# feather_v4.net
KiCad netlist of a schematic drawn in EAGLE
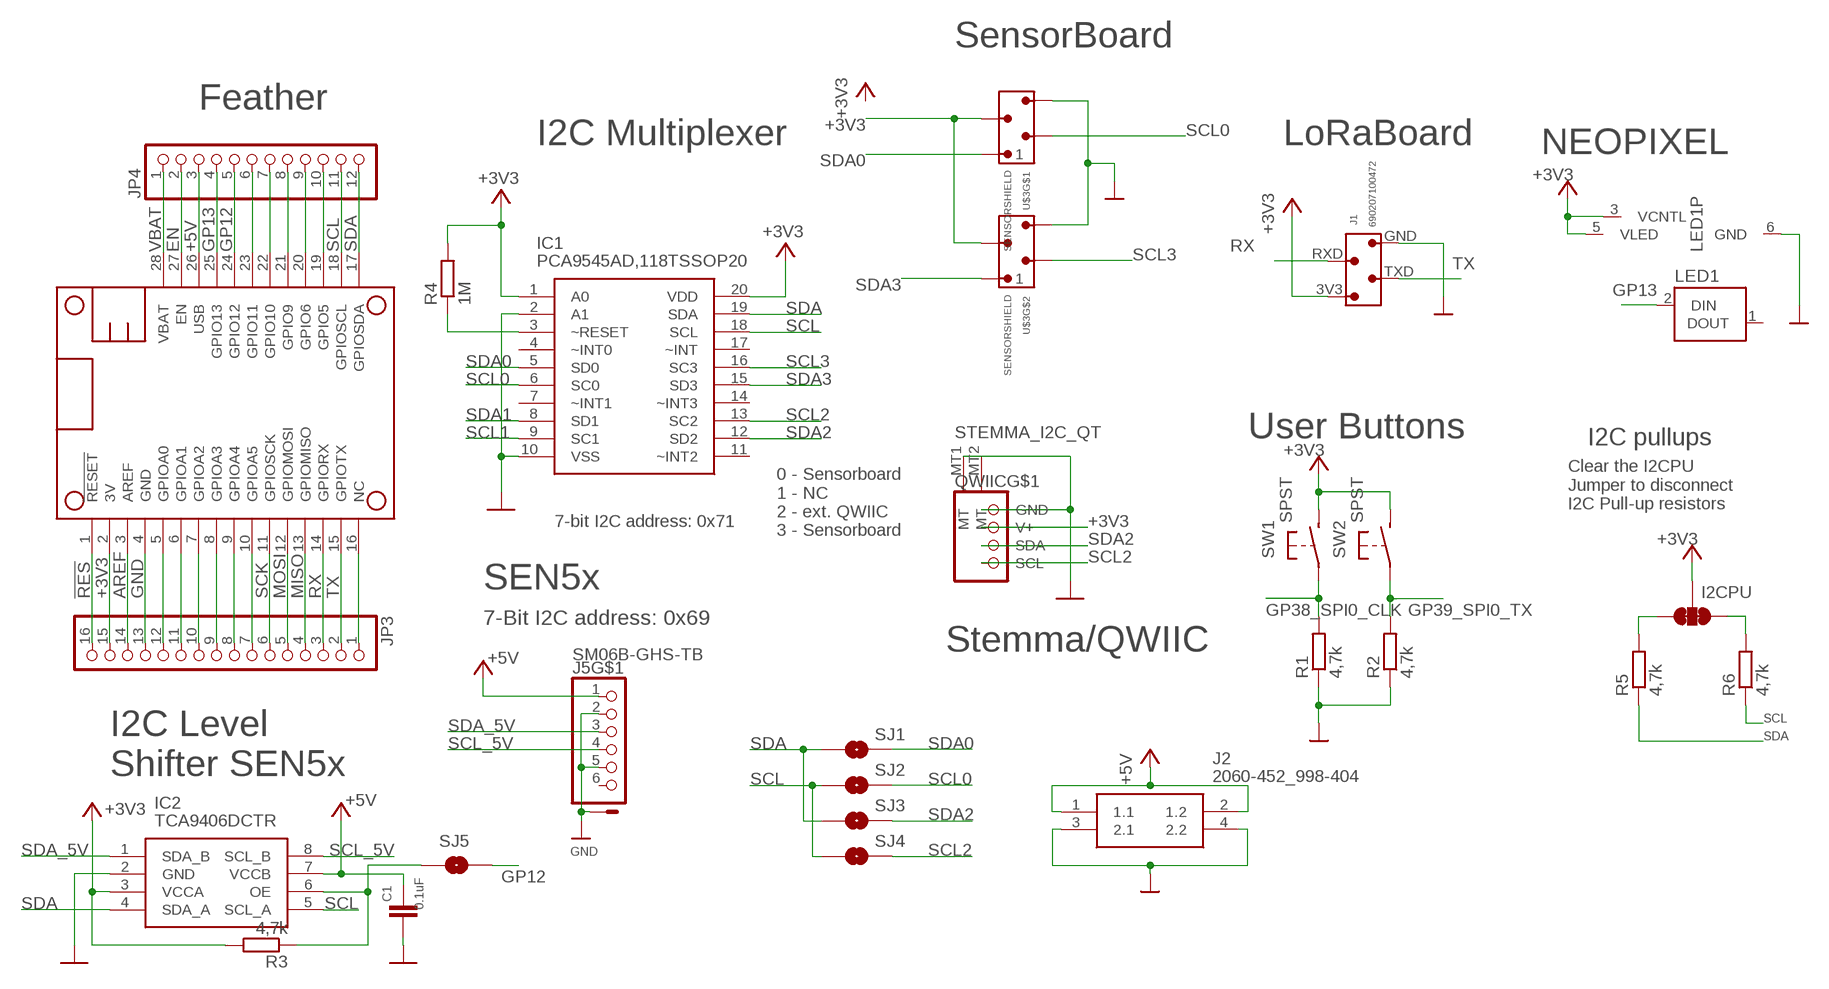
[diagram p0: schematic, sheet 1]

(export (version "E")
  (design (tool "Eeschema 10.0.6"))
  (components
    (comp (ref "C1")
      (value "0.1uF")
      (footprint "eagle-import:C0603")
      (libsource (lib "eagle-import") (part "C-EUC0603"))
    )
    (comp (ref "I2CPU")
      (value "I2C PU")
      (footprint "eagle-import:SMT-JUMPER_3_2-NC_TRACE_SILK")
      (libsource (lib "eagle-import") (part "JUMPER-SMT_3_2-NC_TRACE_SILK"))
    )
    (comp (ref "IC1")
      (value "PCA9545AD,118TSSOP20")
      (footprint "eagle-import:TSSOP20")
      (libsource (lib "eagle-import") (part "PCA9545AD,118TSSOP20"))
    )
    (comp (ref "IC2")
      (value "TCA9406DCTR")
      (footprint "eagle-import:SOP65P400X130-8N")
      (fields (field (name "MOUSER_PART_NUMBER") "595-TCA9406DCTR"))
      (libsource (lib "eagle-import") (part "TCA9406DCTR"))
    )
    (comp (ref "J1")
      (value "690207100472")
      (footprint "eagle-import:LORASHIELD")
      (libsource (lib "eagle-import") (part "LORASHIELD"))
    )
    (comp (ref "J2")
      (value "2060-452_998-404")
      (footprint "eagle-import:2060452998404")
      (fields (field (name "ARROW_PART_NUMBER") "2060-452/998-404"))
      (libsource (lib "eagle-import") (part "2060-452_998-404"))
    )
    (comp (ref "J5")
      (value "SM06B-GHS-TB")
      (footprint "eagle-import:JST-PH-06-SMD")
      (libsource (lib "eagle-import") (part "JST-PH-06-SMDSMD"))
    )
    (comp (ref "JP3")
      (value "HEADER-1X16_76MIL")
      (footprint "eagle-import:1X16_ROUND_76MIL")
      (libsource (lib "eagle-import") (part "HEADER-1X16_76MIL"))
    )
    (comp (ref "JP4")
      (value "HEADER-1X1276MIL")
      (footprint "eagle-import:1X12_ROUND_76MIL")
      (libsource (lib "eagle-import") (part "HEADER-1X1276MIL"))
    )
    (comp (ref "LED1")
      (value "WS2812WS2812")
      (footprint "eagle-import:WS2812")
      (libsource (lib "eagle-import") (part "WS2812WS2812"))
    )
    (comp (ref "MS1")
      (value "FEATHERWING_NODIM")
      (footprint "eagle-import:FEATHERWING_DIM")
      (libsource (lib "eagle-import") (part "FEATHERWING_NODIM"))
    )
    (comp (ref "QWIIC")
      (value "STEMMA_I2C_QT")
      (footprint "eagle-import:JST_SH4")
      (libsource (lib "eagle-import") (part "STEMMA_I2C_QT"))
    )
    (comp (ref "R1")
      (value "4,7k")
      (footprint "eagle-import:R0603")
      (libsource (lib "eagle-import") (part "R-EU_R0603"))
    )
    (comp (ref "R2")
      (value "4,7k")
      (footprint "eagle-import:R0603")
      (libsource (lib "eagle-import") (part "R-EU_R0603"))
    )
    (comp (ref "R3")
      (value "4,7k")
      (footprint "eagle-import:R0603")
      (libsource (lib "eagle-import") (part "R-EU_R0603"))
    )
    (comp (ref "R4")
      (value "1M")
      (footprint "eagle-import:R0603")
      (libsource (lib "eagle-import") (part "R-EU_R0603"))
    )
    (comp (ref "R5")
      (value "4,7k")
      (footprint "eagle-import:R0603")
      (libsource (lib "eagle-import") (part "R-EU_R0603"))
    )
    (comp (ref "R6")
      (value "4,7k")
      (footprint "eagle-import:R0603")
      (libsource (lib "eagle-import") (part "R-EU_R0603"))
    )
    (comp (ref "SJ1")
      (value "SOLDERJUMPERNO")
      (footprint "eagle-import:SJ_2S-NO")
      (libsource (lib "eagle-import") (part "SOLDERJUMPERNO"))
    )
    (comp (ref "SJ2")
      (value "SOLDERJUMPERNO")
      (footprint "eagle-import:SJ_2S-NO")
      (libsource (lib "eagle-import") (part "SOLDERJUMPERNO"))
    )
    (comp (ref "SJ3")
      (value "SOLDERJUMPERNO")
      (footprint "eagle-import:SJ_2S-NO")
      (libsource (lib "eagle-import") (part "SOLDERJUMPERNO"))
    )
    (comp (ref "SJ4")
      (value "SOLDERJUMPERNO")
      (footprint "eagle-import:SJ_2S-NO")
      (libsource (lib "eagle-import") (part "SOLDERJUMPERNO"))
    )
    (comp (ref "SJ5")
      (value "SOLDERJUMPERNO")
      (footprint "eagle-import:SJ_2S-NO")
      (libsource (lib "eagle-import") (part "SOLDERJUMPERNO"))
    )
    (comp (ref "SW1")
      (value "SPST")
      (footprint "eagle-import:DTSM-32S-B")
      (libsource (lib "eagle-import") (part "SPST"))
    )
    (comp (ref "SW2")
      (value "SPST")
      (footprint "eagle-import:DTSM-32S-B")
      (libsource (lib "eagle-import") (part "SPST"))
    )
    (comp (ref "U$3")
      (value "SENSORSHIELD")
      (footprint "eagle-import:SENSORSHIELD")
      (libsource (lib "eagle-import") (part "SENSORSHIELD"))
    )
  )
  (nets
    (net (code "1") (name "+3V3") (class "Default")
      (node (ref "I2CPU") (pin "2") (pinfunction "2_2") (pintype "passive"))
      (node (ref "IC1") (pin "1") (pinfunction "A0_1") (pintype "bidirectional"))
      (node (ref "IC1") (pin "20") (pinfunction "VDD_20") (pintype "bidirectional"))
      (node (ref "IC2") (pin "3") (pinfunction "VCCA_3") (pintype "bidirectional"))
      (node (ref "J1") (pin "3V3") (pinfunction "4_3V3") (pintype "passive"))
      (node (ref "JP3") (pin "15") (pinfunction "15_15") (pintype "passive"))
      (node (ref "LED1") (pin "3") (pinfunction "VCNTL_3") (pintype "power_in"))
      (node (ref "LED1") (pin "5") (pinfunction "VLED_5") (pintype "power_in"))
      (node (ref "MS1") (pin "2") (pinfunction "3V_2") (pintype "power_in"))
      (node (ref "QWIIC") (pin "2") (pinfunction "V+_2") (pintype "passive"))
      (node (ref "R3") (pin "2") (pinfunction "2_2") (pintype "passive"))
      (node (ref "R4") (pin "2") (pinfunction "2_2") (pintype "passive"))
      (node (ref "SW1") (pin "P$2") (pinfunction "S_P$2") (pintype "passive"))
      (node (ref "SW2") (pin "P$2") (pinfunction "S_P$2") (pintype "passive"))
      (node (ref "U$3") (pin "3V3_1") (pinfunction "3_3V3_1") (pintype "passive"))
      (node (ref "U$3") (pin "3V3_2") (pinfunction "3_3V3_2") (pintype "passive"))
    )
    (net (code "2") (name "+5V") (class "Default")
      (node (ref "C1") (pin "1") (pinfunction "1_1") (pintype "passive"))
      (node (ref "IC2") (pin "7") (pinfunction "VCCB_7") (pintype "bidirectional"))
      (node (ref "J2") (pin "1") (pinfunction "1.1_1") (pintype "bidirectional"))
      (node (ref "J2") (pin "2") (pinfunction "1.2_2") (pintype "bidirectional"))
      (node (ref "J5") (pin "1") (pinfunction "1_1") (pintype "passive"))
      (node (ref "JP4") (pin "3") (pinfunction "3_3") (pintype "passive"))
      (node (ref "MS1") (pin "26") (pinfunction "USB_26") (pintype "power_in"))
    )
    (net (code "3") (name "/AREF") (class "Default")
      (node (ref "JP3") (pin "14") (pinfunction "14_14") (pintype "passive"))
      (node (ref "MS1") (pin "3") (pinfunction "AREF_3") (pintype "passive"))
    )
    (net (code "4") (name "/EN") (class "Default")
      (node (ref "JP4") (pin "2") (pinfunction "2_2") (pintype "passive"))
      (node (ref "MS1") (pin "27") (pinfunction "EN_27") (pintype "passive"))
    )
    (net (code "5") (name "/GP12") (class "Default")
      (node (ref "JP4") (pin "5") (pinfunction "5_5") (pintype "passive"))
      (node (ref "MS1") (pin "24") (pinfunction "GPIO12_24") (pintype "bidirectional"))
      (node (ref "SJ5") (pin "2") (pinfunction "2_2") (pintype "passive"))
    )
    (net (code "6") (name "/GP13") (class "Default")
      (node (ref "JP4") (pin "4") (pinfunction "4_4") (pintype "passive"))
      (node (ref "LED1") (pin "2") (pinfunction "DIN_2") (pintype "input"))
      (node (ref "MS1") (pin "25") (pinfunction "GPIO13_25") (pintype "bidirectional"))
    )
    (net (code "7") (name "/GP38_SPI0_CLK") (class "Default")
      (node (ref "R1") (pin "2") (pinfunction "2_2") (pintype "passive"))
      (node (ref "SW1") (pin "P$1") (pinfunction "P_P$1") (pintype "passive"))
    )
    (net (code "8") (name "/GP39_SPI0_TX") (class "Default")
      (node (ref "R2") (pin "2") (pinfunction "2_2") (pintype "passive"))
      (node (ref "SW2") (pin "P$1") (pinfunction "P_P$1") (pintype "passive"))
    )
    (net (code "9") (name "/MISO") (class "Default")
      (node (ref "JP3") (pin "4") (pinfunction "4_4") (pintype "passive"))
      (node (ref "MS1") (pin "13") (pinfunction "GPIOMISO_13") (pintype "bidirectional"))
    )
    (net (code "10") (name "/MOSI") (class "Default")
      (node (ref "JP3") (pin "5") (pinfunction "5_5") (pintype "passive"))
      (node (ref "MS1") (pin "12") (pinfunction "GPIOMOSI_12") (pintype "bidirectional"))
    )
    (net (code "11") (name "/SCK") (class "Default")
      (node (ref "JP3") (pin "6") (pinfunction "6_6") (pintype "passive"))
      (node (ref "MS1") (pin "11") (pinfunction "GPIOSCK_11") (pintype "bidirectional"))
    )
    (net (code "12") (name "/SCL1") (class "Default")
      (node (ref "IC1") (pin "9") (pinfunction "SC1_9") (pintype "bidirectional"))
    )
    (net (code "13") (name "/SCL_5V") (class "Default")
      (node (ref "IC2") (pin "8") (pinfunction "SCL_B_8") (pintype "bidirectional"))
      (node (ref "J5") (pin "4") (pinfunction "4_4") (pintype "passive"))
    )
    (net (code "14") (name "/SDA1") (class "Default")
      (node (ref "IC1") (pin "8") (pinfunction "SD1_8") (pintype "bidirectional"))
    )
    (net (code "15") (name "/SDA_5V") (class "Default")
      (node (ref "IC2") (pin "1") (pinfunction "SDA_B_1") (pintype "bidirectional"))
      (node (ref "J5") (pin "3") (pinfunction "3_3") (pintype "passive"))
    )
    (net (code "16") (name "/VBAT") (class "Default")
      (node (ref "JP4") (pin "1") (pinfunction "1_1") (pintype "passive"))
      (node (ref "MS1") (pin "28") (pinfunction "VBAT_28") (pintype "power_in"))
    )
    (net (code "17") (name "/~{RES}") (class "Default")
      (node (ref "JP3") (pin "16") (pinfunction "16_16") (pintype "passive"))
      (node (ref "MS1") (pin "1") (pinfunction "~{RESET}_1") (pintype "input"))
    )
    (net (code "18") (name "GND") (class "Default")
      (node (ref "C1") (pin "2") (pinfunction "2_2") (pintype "passive"))
      (node (ref "IC1") (pin "10") (pinfunction "VSS_10") (pintype "bidirectional"))
      (node (ref "IC1") (pin "2") (pinfunction "A1_2") (pintype "bidirectional"))
      (node (ref "IC2") (pin "2") (pinfunction "GND_2") (pintype "bidirectional"))
      (node (ref "J1") (pin "GND") (pinfunction "1_GND") (pintype "passive"))
      (node (ref "J2") (pin "3") (pinfunction "2.1_3") (pintype "bidirectional"))
      (node (ref "J2") (pin "4") (pinfunction "2.2_4") (pintype "bidirectional"))
      (node (ref "J5") (pin "2") (pinfunction "2_2") (pintype "passive"))
      (node (ref "J5") (pin "5") (pinfunction "5_5") (pintype "passive"))
      (node (ref "J5") (pin "7") (pinfunction "S_7") (pintype "passive"))
      (node (ref "J5") (pin "8") (pinfunction "S_8") (pintype "passive"))
      (node (ref "JP3") (pin "12") (pinfunction "12_12") (pintype "passive"))
      (node (ref "JP3") (pin "13") (pinfunction "13_13") (pintype "passive"))
      (node (ref "LED1") (pin "6") (pinfunction "GND_6") (pintype "power_in"))
      (node (ref "MS1") (pin "4") (pinfunction "GND_4") (pintype "power_in"))
      (node (ref "MS1") (pin "5") (pinfunction "GPIOA0_5") (pintype "bidirectional"))
      (node (ref "QWIIC") (pin "1") (pinfunction "GND_1") (pintype "passive"))
      (node (ref "QWIIC") (pin "MT1") (pinfunction "MT_MT1") (pintype "bidirectional"))
      (node (ref "QWIIC") (pin "MT2") (pinfunction "MT_MT2") (pintype "bidirectional"))
      (node (ref "R1") (pin "1") (pinfunction "1_1") (pintype "passive"))
      (node (ref "R2") (pin "1") (pinfunction "1_1") (pintype "passive"))
      (node (ref "U$3") (pin "GND_1") (pinfunction "4_GND_1") (pintype "passive"))
      (node (ref "U$3") (pin "GND_2") (pinfunction "4_GND_2") (pintype "passive"))
    )
    (net (code "19") (name "Net-(I2CPU-Pad1)") (class "Default")
      (node (ref "I2CPU") (pin "1") (pinfunction "1_1") (pintype "passive"))
      (node (ref "R6") (pin "2") (pinfunction "2_2") (pintype "passive"))
    )
    (net (code "20") (name "Net-(I2CPU-Pad3)") (class "Default")
      (node (ref "I2CPU") (pin "3") (pinfunction "3_3") (pintype "passive"))
      (node (ref "R5") (pin "2") (pinfunction "2_2") (pintype "passive"))
    )
    (net (code "21") (name "Net-(IC1-~{RESET})") (class "Default")
      (node (ref "IC1") (pin "3") (pinfunction "~{RESET}_3") (pintype "bidirectional"))
      (node (ref "R4") (pin "1") (pinfunction "1_1") (pintype "passive"))
    )
    (net (code "22") (name "Net-(IC2-OE)") (class "Default")
      (node (ref "IC2") (pin "6") (pinfunction "OE_6") (pintype "bidirectional"))
      (node (ref "R3") (pin "1") (pinfunction "1_1") (pintype "passive"))
      (node (ref "SJ5") (pin "1") (pinfunction "1_1") (pintype "passive"))
    )
    (net (code "23") (name "Net-(MS1-GPIO5)") (class "Default")
      (node (ref "JP4") (pin "10") (pinfunction "10_10") (pintype "passive"))
      (node (ref "MS1") (pin "19") (pinfunction "GPIO5_19") (pintype "bidirectional"))
    )
    (net (code "24") (name "Net-(MS1-GPIO6)") (class "Default")
      (node (ref "JP4") (pin "9") (pinfunction "9_9") (pintype "passive"))
      (node (ref "MS1") (pin "20") (pinfunction "GPIO6_20") (pintype "bidirectional"))
    )
    (net (code "25") (name "Net-(MS1-GPIO9)") (class "Default")
      (node (ref "JP4") (pin "8") (pinfunction "8_8") (pintype "passive"))
      (node (ref "MS1") (pin "21") (pinfunction "GPIO9_21") (pintype "bidirectional"))
    )
    (net (code "26") (name "Net-(MS1-GPIO10)") (class "Default")
      (node (ref "JP4") (pin "7") (pinfunction "7_7") (pintype "passive"))
      (node (ref "MS1") (pin "22") (pinfunction "GPIO10_22") (pintype "bidirectional"))
    )
    (net (code "27") (name "Net-(MS1-GPIO11)") (class "Default")
      (node (ref "JP4") (pin "6") (pinfunction "6_6") (pintype "passive"))
      (node (ref "MS1") (pin "23") (pinfunction "GPIO11_23") (pintype "bidirectional"))
    )
    (net (code "28") (name "Net-(MS1-GPIOA1)") (class "Default")
      (node (ref "JP3") (pin "11") (pinfunction "11_11") (pintype "passive"))
      (node (ref "MS1") (pin "6") (pinfunction "GPIOA1_6") (pintype "bidirectional"))
    )
    (net (code "29") (name "Net-(MS1-GPIOA2)") (class "Default")
      (node (ref "JP3") (pin "10") (pinfunction "10_10") (pintype "passive"))
      (node (ref "MS1") (pin "7") (pinfunction "GPIOA2_7") (pintype "bidirectional"))
    )
    (net (code "30") (name "Net-(MS1-GPIOA3)") (class "Default")
      (node (ref "JP3") (pin "9") (pinfunction "9_9") (pintype "passive"))
      (node (ref "MS1") (pin "8") (pinfunction "GPIOA3_8") (pintype "bidirectional"))
    )
    (net (code "31") (name "Net-(MS1-GPIOA4)") (class "Default")
      (node (ref "JP3") (pin "8") (pinfunction "8_8") (pintype "passive"))
      (node (ref "MS1") (pin "9") (pinfunction "GPIOA4_9") (pintype "bidirectional"))
    )
    (net (code "32") (name "Net-(MS1-GPIOA5)") (class "Default")
      (node (ref "JP3") (pin "7") (pinfunction "7_7") (pintype "passive"))
      (node (ref "MS1") (pin "10") (pinfunction "GPIOA5_10") (pintype "bidirectional"))
    )
    (net (code "33") (name "Net-(MS1-NC)") (class "Default")
      (node (ref "JP3") (pin "1") (pinfunction "1_1") (pintype "passive"))
      (node (ref "MS1") (pin "16") (pinfunction "NC_16") (pintype "passive"))
    )
    (net (code "34") (name "RX") (class "Default")
      (node (ref "J1") (pin "RXD") (pinfunction "2_RXD") (pintype "passive"))
      (node (ref "JP3") (pin "3") (pinfunction "3_3") (pintype "passive"))
      (node (ref "MS1") (pin "14") (pinfunction "GPIORX_14") (pintype "bidirectional"))
    )
    (net (code "35") (name "SCL") (class "Default")
      (node (ref "IC1") (pin "18") (pinfunction "SCL_18") (pintype "bidirectional"))
      (node (ref "IC2") (pin "5") (pinfunction "SCL_A_5") (pintype "bidirectional"))
      (node (ref "JP4") (pin "11") (pinfunction "11_11") (pintype "passive"))
      (node (ref "MS1") (pin "18") (pinfunction "GPIOSCL_18") (pintype "bidirectional"))
      (node (ref "R6") (pin "1") (pinfunction "1_1") (pintype "passive"))
      (node (ref "SJ2") (pin "1") (pinfunction "1_1") (pintype "passive"))
      (node (ref "SJ4") (pin "1") (pinfunction "1_1") (pintype "passive"))
    )
    (net (code "36") (name "SCL0") (class "Default")
      (node (ref "IC1") (pin "6") (pinfunction "SC0_6") (pintype "bidirectional"))
      (node (ref "SJ2") (pin "2") (pinfunction "2_2") (pintype "passive"))
      (node (ref "U$3") (pin "SCL0") (pinfunction "2_SCL0") (pintype "passive"))
    )
    (net (code "37") (name "SCL2") (class "Default")
      (node (ref "IC1") (pin "13") (pinfunction "SC2_13") (pintype "bidirectional"))
      (node (ref "QWIIC") (pin "4") (pinfunction "SCL_4") (pintype "passive"))
      (node (ref "SJ4") (pin "2") (pinfunction "2_2") (pintype "passive"))
    )
    (net (code "38") (name "SCL3") (class "Default")
      (node (ref "IC1") (pin "16") (pinfunction "SC3_16") (pintype "bidirectional"))
      (node (ref "U$3") (pin "SCL1") (pinfunction "2_SCL1") (pintype "passive"))
    )
    (net (code "39") (name "SDA") (class "Default")
      (node (ref "IC1") (pin "19") (pinfunction "SDA_19") (pintype "bidirectional"))
      (node (ref "IC2") (pin "4") (pinfunction "SDA_A_4") (pintype "bidirectional"))
      (node (ref "JP4") (pin "12") (pinfunction "12_12") (pintype "passive"))
      (node (ref "MS1") (pin "17") (pinfunction "GPIOSDA_17") (pintype "bidirectional"))
      (node (ref "R5") (pin "1") (pinfunction "1_1") (pintype "passive"))
      (node (ref "SJ1") (pin "1") (pinfunction "1_1") (pintype "passive"))
      (node (ref "SJ3") (pin "1") (pinfunction "1_1") (pintype "passive"))
    )
    (net (code "40") (name "SDA0") (class "Default")
      (node (ref "IC1") (pin "5") (pinfunction "SD0_5") (pintype "bidirectional"))
      (node (ref "SJ1") (pin "2") (pinfunction "2_2") (pintype "passive"))
      (node (ref "U$3") (pin "SDA0") (pinfunction "1_SDA0") (pintype "passive"))
    )
    (net (code "41") (name "SDA2") (class "Default")
      (node (ref "IC1") (pin "12") (pinfunction "SD2_12") (pintype "bidirectional"))
      (node (ref "QWIIC") (pin "3") (pinfunction "SDA_3") (pintype "passive"))
      (node (ref "SJ3") (pin "2") (pinfunction "2_2") (pintype "passive"))
    )
    (net (code "42") (name "SDA3") (class "Default")
      (node (ref "IC1") (pin "15") (pinfunction "SD3_15") (pintype "bidirectional"))
      (node (ref "U$3") (pin "SDA1") (pinfunction "1_SDA1") (pintype "passive"))
    )
    (net (code "43") (name "TX") (class "Default")
      (node (ref "J1") (pin "TXD") (pinfunction "3_TXD") (pintype "passive"))
      (node (ref "JP3") (pin "2") (pinfunction "2_2") (pintype "passive"))
      (node (ref "MS1") (pin "15") (pinfunction "GPIOTX_15") (pintype "bidirectional"))
    )
    (net (code "44") (name "unconnected-(IC1-~{INT0}-Pad4)") (class "Default")
      (node (ref "IC1") (pin "4") (pinfunction "~{INT0}_4") (pintype "bidirectional"))
    )
    (net (code "45") (name "unconnected-(IC1-~{INT1}-Pad7)") (class "Default")
      (node (ref "IC1") (pin "7") (pinfunction "~{INT1}_7") (pintype "bidirectional"))
    )
    (net (code "46") (name "unconnected-(IC1-~{INT2}-Pad11)") (class "Default")
      (node (ref "IC1") (pin "11") (pinfunction "~{INT2}_11") (pintype "bidirectional"))
    )
    (net (code "47") (name "unconnected-(IC1-~{INT3}-Pad14)") (class "Default")
      (node (ref "IC1") (pin "14") (pinfunction "~{INT3}_14") (pintype "bidirectional"))
    )
    (net (code "48") (name "unconnected-(IC1-~{INT}-Pad17)") (class "Default")
      (node (ref "IC1") (pin "17") (pinfunction "~{INT}_17") (pintype "bidirectional"))
    )
    (net (code "49") (name "unconnected-(J5-Pad6)") (class "Default")
      (node (ref "J5") (pin "6") (pinfunction "6_6") (pintype "passive"))
    )
    (net (code "50") (name "unconnected-(LED1B-DOUT-Pad1)") (class "Default")
      (node (ref "LED1") (pin "1") (pinfunction "DOUT_1") (pintype "output"))
    )
  )
)
